# mapleCUL_small-V2_0_019.net
KiCad netlist of a schematic drawn in EAGLE
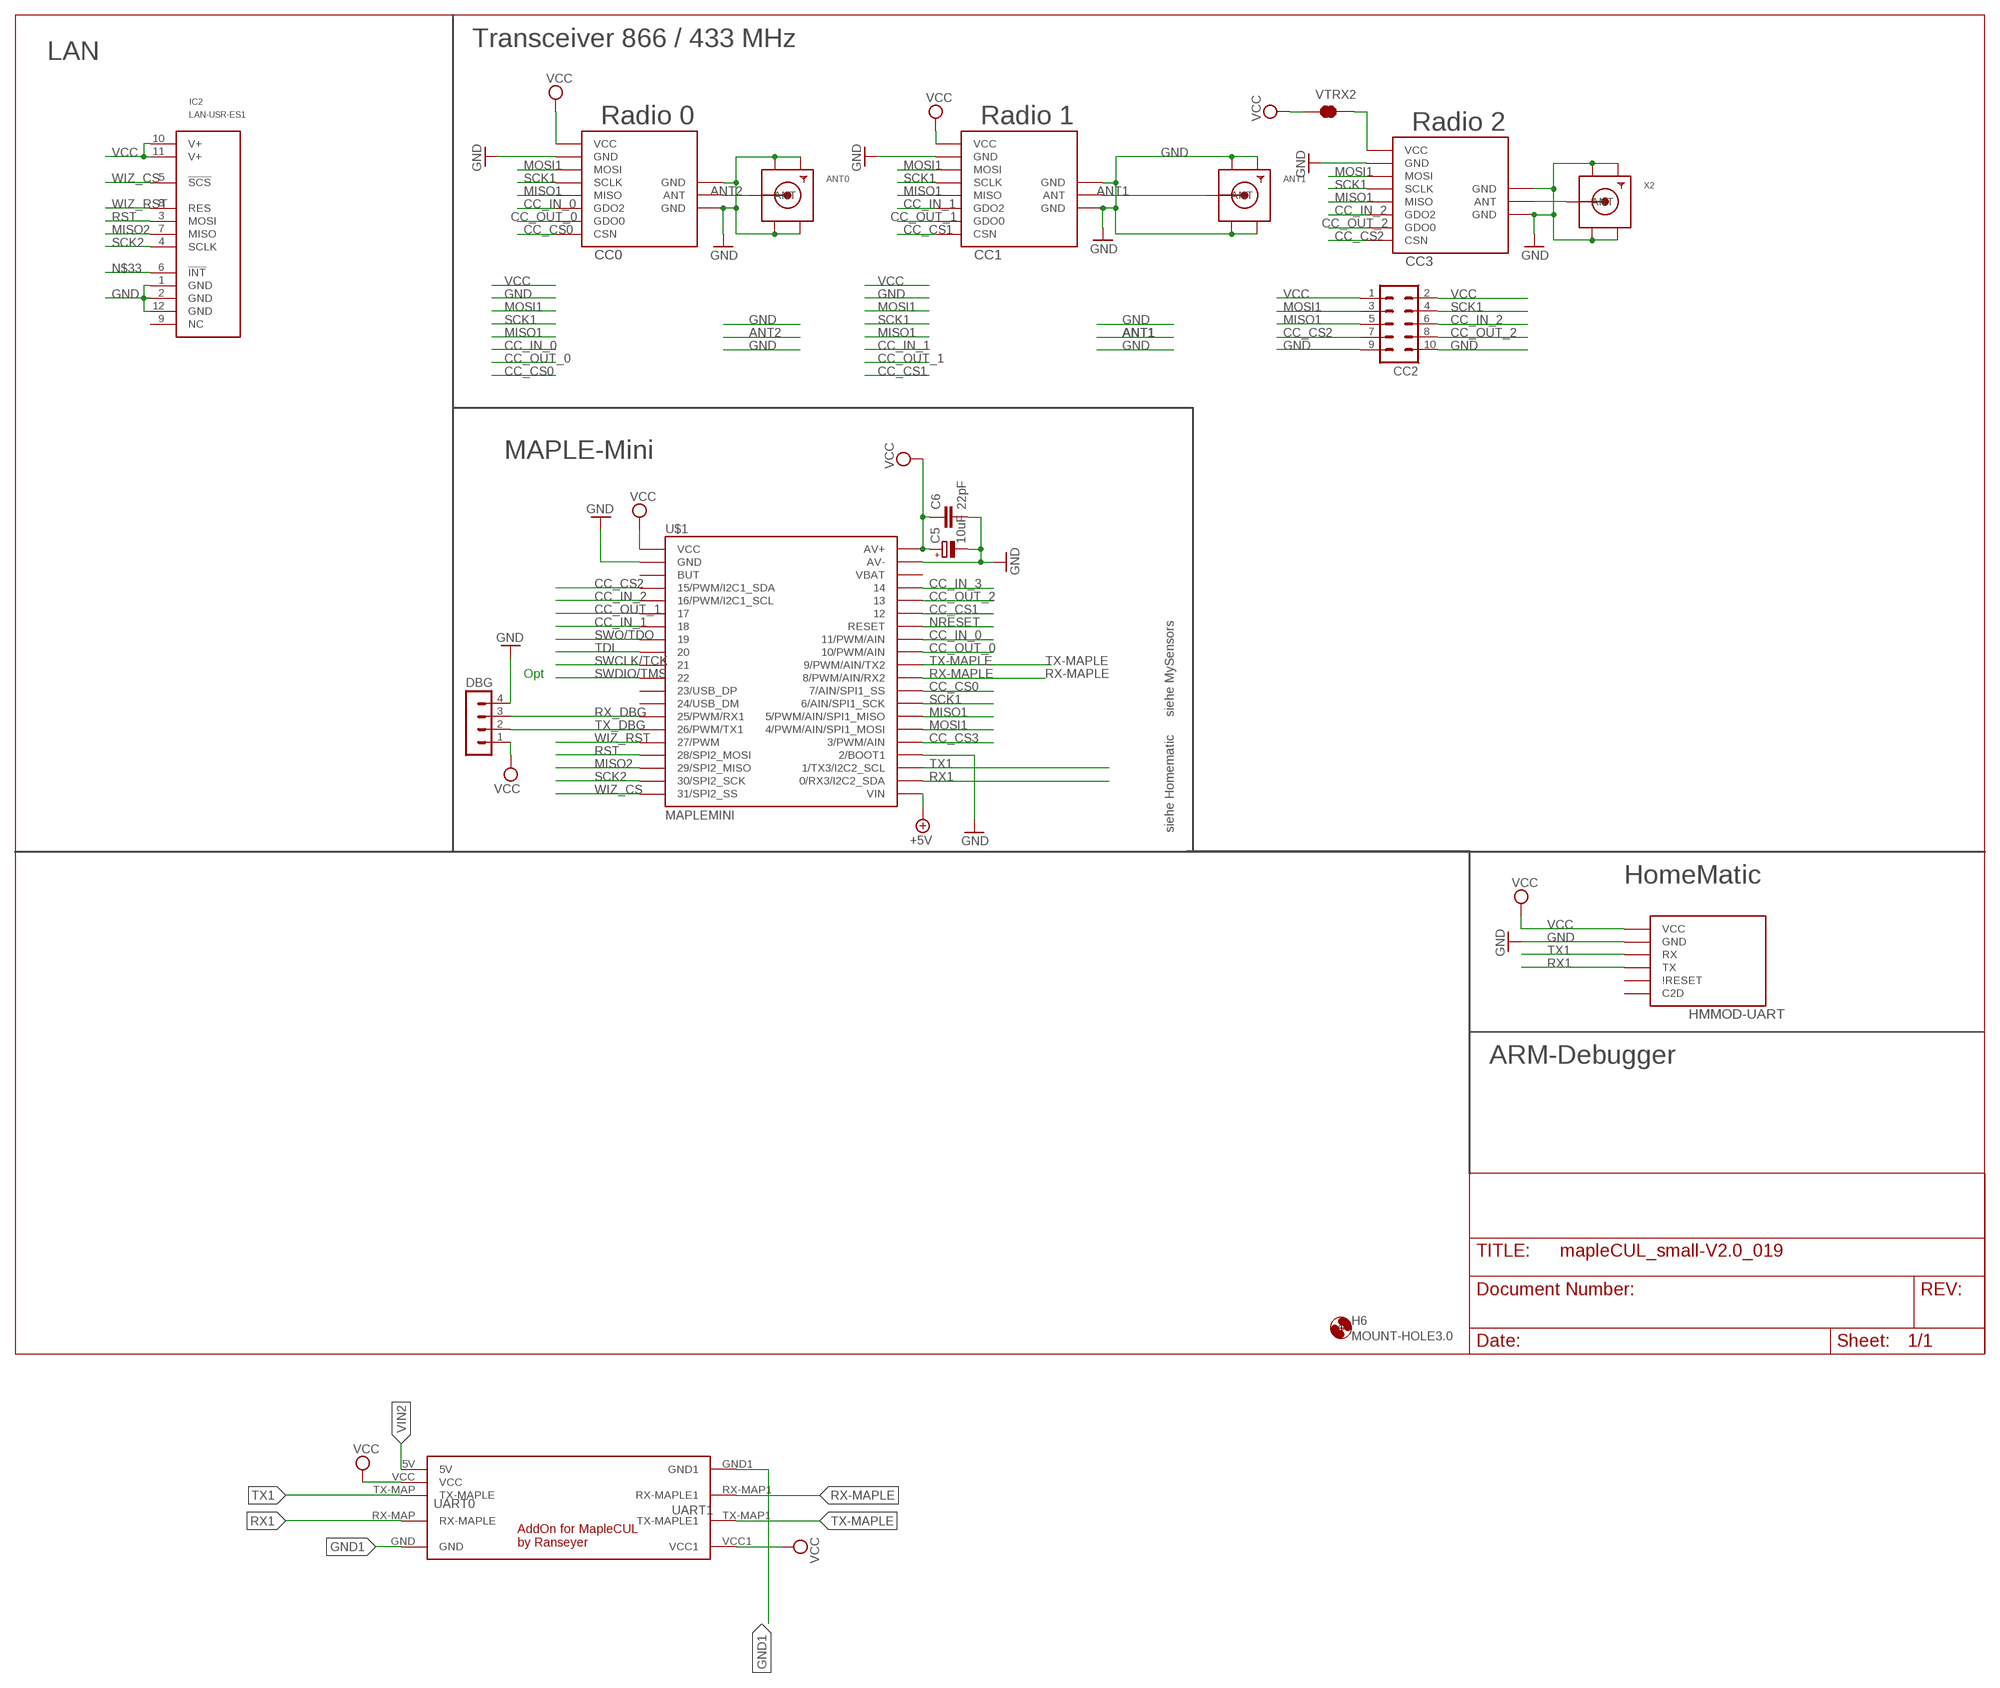
[diagram p0: schematic, sheet 1]

(export (version "E")
  (design (tool "Eeschema 10.0.6"))
  (components
    (comp (ref "ANT0")
      (value "SMACONNECTOR_EDGE_UFL")
      (footprint "eagle-import:SMA_EDGELAUNCH_UFL")
      (libsource (lib "eagle-import") (part "SMACONNECTOR_EDGE_UFL"))
    )
    (comp (ref "ANT1")
      (value "SMACONNECTOR_EDGE_UFL")
      (footprint "eagle-import:SMA_EDGELAUNCH_UFL")
      (libsource (lib "eagle-import") (part "SMACONNECTOR_EDGE_UFL"))
    )
    (comp (ref "C5")
      (value "10uF")
      (footprint "eagle-import:R_2012-12W")
      (libsource (lib "eagle-import") (part "CPOL-EUR/2012-12W"))
    )
    (comp (ref "C6")
      (value "22pF")
      (footprint "eagle-import:C0805")
      (libsource (lib "eagle-import") (part "C-EUC0805"))
    )
    (comp (ref "CC0")
      (value "CC1101")
      (footprint "eagle-import:CC1101_MODULE1_SMD")
      (libsource (lib "eagle-import") (part "CC1101_MODULE1SMD"))
    )
    (comp (ref "CC1")
      (value "CC1101_MODULE1SMD")
      (footprint "eagle-import:CC1101_MODULE1_SMD")
      (libsource (lib "eagle-import") (part "CC1101_MODULE1SMD"))
    )
    (comp (ref "CC2")
      (value "MA05-2")
      (footprint "eagle-import:MA05-2")
      (libsource (lib "eagle-import") (part "MA05-2"))
    )
    (comp (ref "CC3")
      (value "CC1101_MODULE1SMD")
      (footprint "eagle-import:CC1101_MODULE1_SMD")
      (libsource (lib "eagle-import") (part "CC1101_MODULE1SMD"))
    )
    (comp (ref "DBG")
      (value "MA04-1")
      (footprint "eagle-import:MA04-1")
      (libsource (lib "eagle-import") (part "MA04-1"))
    )
    (comp (ref "H6")
      (value "MOUNT-HOLE3.0")
      (footprint "eagle-import:3,0")
      (libsource (lib "eagle-import") (part "MOUNT-HOLE3.0"))
    )
    (comp (ref "HMMOD-UART")
      (value "HM-MOD-UARTDIL")
      (footprint "eagle-import:HM-MOD-UART-DIL")
      (libsource (lib "eagle-import") (part "HM-MOD-UARTDIL"))
    )
    (comp (ref "IC2")
      (value "LAN-USR-ES1")
      (footprint "eagle-import:USR-ES1")
      (libsource (lib "eagle-import") (part "LAN-USR-ES1"))
    )
    (comp (ref "U$1")
      (value "MAPLEMINI")
      (footprint "eagle-import:20-DIP")
      (libsource (lib "eagle-import") (part "MAPLEMINI"))
    )
    (comp (ref "U$3")
      (value "MAPLE-CUL-ADDON-V01")
      (footprint "eagle-import:MAPLE-CUL-V01")
      (libsource (lib "eagle-import") (part "MAPLE-CUL-ADDON-V01"))
    )
    (comp (ref "VTRX2")
      (value "JUMPER-SMT_2_NC_TRACE_SILK")
      (footprint "eagle-import:SMT-JUMPER_2_NC_TRACE_SILK")
      (libsource (lib "eagle-import") (part "JUMPER-SMT_2_NC_TRACE_SILK"))
    )
    (comp (ref "X2")
      (value "SMACONNECTOR_EDGE")
      (footprint "eagle-import:SMA_EDGELAUNCH")
      (libsource (lib "eagle-import") (part "SMACONNECTOR_EDGE"))
    )
  )
  (nets
    (net (code "1") (name "+5V") (class "Default")
      (node (ref "U$1") (pin "21") (pinfunction "VIN_21") (pintype "bidirectional"))
    )
    (net (code "2") (name "/ANT1") (class "Default")
      (node (ref "ANT1") (pin "P") (pinfunction "ANT_P") (pintype "bidirectional"))
      (node (ref "CC1") (pin "ANT") (pinfunction "ANT_ANT") (pintype "output"))
    )
    (net (code "3") (name "/ANT2") (class "Default")
      (node (ref "ANT0") (pin "P") (pinfunction "ANT_P") (pintype "bidirectional"))
      (node (ref "CC0") (pin "ANT") (pinfunction "ANT_ANT") (pintype "output"))
    )
    (net (code "4") (name "/CC_CS0") (class "Default")
      (node (ref "CC0") (pin "CSN") (pinfunction "CSN_CSN") (pintype "bidirectional"))
      (node (ref "U$1") (pin "29") (pinfunction "7/AIN/SPI1_SS_29") (pintype "bidirectional"))
    )
    (net (code "5") (name "/CC_CS1") (class "Default")
      (node (ref "CC1") (pin "CSN") (pinfunction "CSN_CSN") (pintype "bidirectional"))
      (node (ref "U$1") (pin "35") (pinfunction "12_35") (pintype "bidirectional"))
    )
    (net (code "6") (name "/CC_CS2") (class "Default")
      (node (ref "CC2") (pin "7") (pinfunction "7_7") (pintype "passive"))
      (node (ref "CC3") (pin "CSN") (pinfunction "CSN_CSN") (pintype "bidirectional"))
      (node (ref "U$1") (pin "4") (pinfunction "15/PWM/I2C1_SDA_4") (pintype "bidirectional"))
    )
    (net (code "7") (name "/CC_CS3") (class "Default")
      (node (ref "U$1") (pin "25") (pinfunction "3/PWM/AIN_25") (pintype "bidirectional"))
    )
    (net (code "8") (name "/CC_IN_0") (class "Default")
      (node (ref "CC0") (pin "GDO2") (pinfunction "GDO2_GDO2") (pintype "bidirectional"))
      (node (ref "U$1") (pin "33") (pinfunction "11/PWM/AIN_33") (pintype "bidirectional"))
    )
    (net (code "9") (name "/CC_IN_1") (class "Default")
      (node (ref "CC1") (pin "GDO2") (pinfunction "GDO2_GDO2") (pintype "bidirectional"))
      (node (ref "U$1") (pin "7") (pinfunction "18_7") (pintype "bidirectional"))
    )
    (net (code "10") (name "/CC_IN_2") (class "Default")
      (node (ref "CC2") (pin "6") (pinfunction "6_6") (pintype "passive"))
      (node (ref "CC3") (pin "GDO2") (pinfunction "GDO2_GDO2") (pintype "bidirectional"))
      (node (ref "U$1") (pin "5") (pinfunction "16/PWM/I2C1_SCL_5") (pintype "bidirectional"))
    )
    (net (code "11") (name "/CC_IN_3") (class "Default")
      (node (ref "U$1") (pin "37") (pinfunction "14_37") (pintype "bidirectional"))
    )
    (net (code "12") (name "/CC_OUT_0") (class "Default")
      (node (ref "CC0") (pin "GDO0") (pinfunction "GDO0_GDO0") (pintype "bidirectional"))
      (node (ref "U$1") (pin "32") (pinfunction "10/PWM/AIN_32") (pintype "bidirectional"))
    )
    (net (code "13") (name "/CC_OUT_1") (class "Default")
      (node (ref "CC1") (pin "GDO0") (pinfunction "GDO0_GDO0") (pintype "bidirectional"))
      (node (ref "U$1") (pin "6") (pinfunction "17_6") (pintype "bidirectional"))
    )
    (net (code "14") (name "/CC_OUT_2") (class "Default")
      (node (ref "CC2") (pin "8") (pinfunction "8_8") (pintype "passive"))
      (node (ref "CC3") (pin "GDO0") (pinfunction "GDO0_GDO0") (pintype "bidirectional"))
      (node (ref "U$1") (pin "36") (pinfunction "13_36") (pintype "bidirectional"))
    )
    (net (code "15") (name "/MISO1") (class "Default")
      (node (ref "CC0") (pin "MISO") (pinfunction "MISO_MISO") (pintype "bidirectional"))
      (node (ref "CC1") (pin "MISO") (pinfunction "MISO_MISO") (pintype "bidirectional"))
      (node (ref "CC2") (pin "5") (pinfunction "5_5") (pintype "passive"))
      (node (ref "CC3") (pin "MISO") (pinfunction "MISO_MISO") (pintype "bidirectional"))
      (node (ref "U$1") (pin "27") (pinfunction "5/PWM/AIN/SPI1_MISO_27") (pintype "bidirectional"))
    )
    (net (code "16") (name "/MISO2") (class "Default")
      (node (ref "IC2") (pin "7") (pinfunction "MISO_7") (pintype "bidirectional"))
      (node (ref "U$1") (pin "18") (pinfunction "29/SPI2_MISO_18") (pintype "bidirectional"))
    )
    (net (code "17") (name "/MOSI1") (class "Default")
      (node (ref "CC0") (pin "MOSI") (pinfunction "MOSI_MOSI") (pintype "bidirectional"))
      (node (ref "CC1") (pin "MOSI") (pinfunction "MOSI_MOSI") (pintype "bidirectional"))
      (node (ref "CC2") (pin "3") (pinfunction "3_3") (pintype "passive"))
      (node (ref "CC3") (pin "MOSI") (pinfunction "MOSI_MOSI") (pintype "bidirectional"))
      (node (ref "U$1") (pin "26") (pinfunction "4/PWM/AIN/SPI1_MOSI_26") (pintype "bidirectional"))
    )
    (net (code "18") (name "/N$33") (class "Default")
      (node (ref "IC2") (pin "6") (pinfunction "~{INT}_6") (pintype "output"))
    )
    (net (code "19") (name "/NRESET") (class "Default")
      (node (ref "U$1") (pin "34") (pinfunction "RESET_34") (pintype "bidirectional"))
    )
    (net (code "20") (name "/RST") (class "Default")
      (node (ref "IC2") (pin "3") (pinfunction "MOSI_3") (pintype "bidirectional"))
      (node (ref "U$1") (pin "17") (pinfunction "28/SPI2_MOSI_17") (pintype "bidirectional"))
    )
    (net (code "21") (name "/RX_DBG") (class "Default")
      (node (ref "DBG") (pin "3") (pinfunction "3_3") (pintype "passive"))
      (node (ref "U$1") (pin "14") (pinfunction "25/PWM/RX1_14") (pintype "bidirectional"))
    )
    (net (code "22") (name "/SCK1") (class "Default")
      (node (ref "CC0") (pin "SCLK") (pinfunction "SCLK_SCLK") (pintype "bidirectional"))
      (node (ref "CC1") (pin "SCLK") (pinfunction "SCLK_SCLK") (pintype "bidirectional"))
      (node (ref "CC2") (pin "4") (pinfunction "4_4") (pintype "passive"))
      (node (ref "CC3") (pin "SCLK") (pinfunction "SCLK_SCLK") (pintype "bidirectional"))
      (node (ref "U$1") (pin "28") (pinfunction "6/AIN/SPI1_SCK_28") (pintype "bidirectional"))
    )
    (net (code "23") (name "/SCK2") (class "Default")
      (node (ref "IC2") (pin "4") (pinfunction "SCLK_4") (pintype "input"))
      (node (ref "U$1") (pin "19") (pinfunction "30/SPI2_SCK_19") (pintype "bidirectional"))
    )
    (net (code "24") (name "/SWCLK{slash}TCK") (class "Default")
      (node (ref "U$1") (pin "10") (pinfunction "21_10") (pintype "bidirectional"))
    )
    (net (code "25") (name "/SWDIO{slash}TMS") (class "Default")
      (node (ref "U$1") (pin "11") (pinfunction "22_11") (pintype "bidirectional"))
    )
    (net (code "26") (name "/SWO{slash}TDO") (class "Default")
      (node (ref "U$1") (pin "8") (pinfunction "19_8") (pintype "bidirectional"))
    )
    (net (code "27") (name "/TDI") (class "Default")
      (node (ref "U$1") (pin "9") (pinfunction "20_9") (pintype "bidirectional"))
    )
    (net (code "28") (name "/TX_DBG") (class "Default")
      (node (ref "DBG") (pin "2") (pinfunction "2_2") (pintype "passive"))
      (node (ref "U$1") (pin "15") (pinfunction "26/PWM/TX1_15") (pintype "bidirectional"))
    )
    (net (code "29") (name "/WIZ_CS") (class "Default")
      (node (ref "IC2") (pin "5") (pinfunction "~{SCS}_5") (pintype "input"))
      (node (ref "U$1") (pin "20") (pinfunction "31/SPI2_SS_20") (pintype "bidirectional"))
    )
    (net (code "30") (name "/WIZ_RST") (class "Default")
      (node (ref "IC2") (pin "8") (pinfunction "RES_8") (pintype "input"))
      (node (ref "U$1") (pin "16") (pinfunction "27/PWM_16") (pintype "bidirectional"))
    )
    (net (code "31") (name "GND") (class "Default")
      (node (ref "ANT0") (pin "GND@1") (pinfunction "GND1_GND@1") (pintype "power_in"))
      (node (ref "ANT0") (pin "GND@2") (pinfunction "GND2_GND@2") (pintype "power_in"))
      (node (ref "ANT0") (pin "GND@3") (pinfunction "GND3_GND@3") (pintype "power_in"))
      (node (ref "ANT0") (pin "GND@4") (pinfunction "GND4_GND@4") (pintype "power_in"))
      (node (ref "ANT1") (pin "GND@1") (pinfunction "GND1_GND@1") (pintype "power_in"))
      (node (ref "ANT1") (pin "GND@2") (pinfunction "GND2_GND@2") (pintype "power_in"))
      (node (ref "ANT1") (pin "GND@3") (pinfunction "GND3_GND@3") (pintype "power_in"))
      (node (ref "ANT1") (pin "GND@4") (pinfunction "GND4_GND@4") (pintype "power_in"))
      (node (ref "C5") (pin "-") (pinfunction "-_-") (pintype "passive"))
      (node (ref "C6") (pin "2") (pinfunction "2_2") (pintype "passive"))
      (node (ref "CC0") (pin "GND@0") (pinfunction "GND_GND@0") (pintype "power_in"))
      (node (ref "CC0") (pin "GND@1") (pinfunction "GND_GND@1") (pintype "power_in"))
      (node (ref "CC0") (pin "GND@2") (pinfunction "GND_GND@2") (pintype "power_in"))
      (node (ref "CC1") (pin "GND@0") (pinfunction "GND_GND@0") (pintype "power_in"))
      (node (ref "CC1") (pin "GND@1") (pinfunction "GND_GND@1") (pintype "power_in"))
      (node (ref "CC1") (pin "GND@2") (pinfunction "GND_GND@2") (pintype "power_in"))
      (node (ref "CC2") (pin "10") (pinfunction "10_10") (pintype "passive"))
      (node (ref "CC2") (pin "9") (pinfunction "9_9") (pintype "passive"))
      (node (ref "CC3") (pin "GND@0") (pinfunction "GND_GND@0") (pintype "power_in"))
      (node (ref "CC3") (pin "GND@1") (pinfunction "GND_GND@1") (pintype "power_in"))
      (node (ref "CC3") (pin "GND@2") (pinfunction "GND_GND@2") (pintype "power_in"))
      (node (ref "DBG") (pin "4") (pinfunction "4_4") (pintype "passive"))
      (node (ref "HMMOD-UART") (pin "2") (pinfunction "GND_2") (pintype "power_in"))
      (node (ref "IC2") (pin "1") (pinfunction "GND_1") (pintype "power_in"))
      (node (ref "IC2") (pin "12") (pinfunction "GND_12") (pintype "power_in"))
      (node (ref "IC2") (pin "2") (pinfunction "GND_2") (pintype "power_in"))
      (node (ref "U$1") (pin "2") (pinfunction "GND_2") (pintype "bidirectional"))
      (node (ref "U$1") (pin "24") (pinfunction "2/BOOT1_24") (pintype "bidirectional"))
      (node (ref "U$1") (pin "39") (pinfunction "AV-_39") (pintype "bidirectional"))
      (node (ref "X2") (pin "GND@1") (pinfunction "GND4_GND@1") (pintype "power_in"))
      (node (ref "X2") (pin "GND@2") (pinfunction "GND3_GND@2") (pintype "power_in"))
      (node (ref "X2") (pin "GND@3") (pinfunction "GND2_GND@3") (pintype "power_in"))
      (node (ref "X2") (pin "GND@4") (pinfunction "GND1_GND@4") (pintype "power_in"))
    )
    (net (code "32") (name "GND1") (class "Default")
      (node (ref "U$3") (pin "GND") (pinfunction "GND_GND") (pintype "bidirectional"))
      (node (ref "U$3") (pin "GND1") (pinfunction "GND1_GND1") (pintype "bidirectional"))
    )
    (net (code "33") (name "Net-(CC3-PadVCC)") (class "Default")
      (node (ref "CC3") (pin "VCC") (pinfunction "VCC_VCC") (pintype "power_in"))
      (node (ref "VTRX2") (pin "2") (pinfunction "2_2") (pintype "passive"))
    )
    (net (code "34") (name "Net-(X2-ANT)") (class "Default")
      (node (ref "CC3") (pin "ANT") (pinfunction "ANT_ANT") (pintype "output"))
      (node (ref "X2") (pin "P") (pinfunction "ANT_P") (pintype "bidirectional"))
    )
    (net (code "35") (name "RX-MAPLE") (class "Default")
      (node (ref "U$1") (pin "30") (pinfunction "8/PWM/AIN/RX2_30") (pintype "bidirectional"))
      (node (ref "U$3") (pin "RX-MAP1") (pinfunction "RX-MAPLE1_RX-MAP1") (pintype "bidirectional"))
    )
    (net (code "36") (name "RX1") (class "Default")
      (node (ref "HMMOD-UART") (pin "5") (pinfunction "TX_5") (pintype "bidirectional"))
      (node (ref "U$1") (pin "22") (pinfunction "0/RX3/I2C2_SDA_22") (pintype "bidirectional"))
      (node (ref "U$3") (pin "RX-MAP") (pinfunction "RX-MAPLE_RX-MAP") (pintype "bidirectional"))
    )
    (net (code "37") (name "TX-MAPLE") (class "Default")
      (node (ref "U$1") (pin "31") (pinfunction "9/PWM/AIN/TX2_31") (pintype "bidirectional"))
      (node (ref "U$3") (pin "TX-MAP1") (pinfunction "TX-MAPLE1_TX-MAP1") (pintype "bidirectional"))
    )
    (net (code "38") (name "TX1") (class "Default")
      (node (ref "HMMOD-UART") (pin "6") (pinfunction "RX_6") (pintype "bidirectional"))
      (node (ref "U$1") (pin "23") (pinfunction "1/TX3/I2C2_SCL_23") (pintype "bidirectional"))
      (node (ref "U$3") (pin "TX-MAP") (pinfunction "TX-MAPLE_TX-MAP") (pintype "bidirectional"))
    )
    (net (code "39") (name "VCC") (class "Default")
      (node (ref "C5") (pin "+") (pinfunction "+_+") (pintype "passive"))
      (node (ref "C6") (pin "1") (pinfunction "1_1") (pintype "passive"))
      (node (ref "CC0") (pin "VCC") (pinfunction "VCC_VCC") (pintype "power_in"))
      (node (ref "CC1") (pin "VCC") (pinfunction "VCC_VCC") (pintype "power_in"))
      (node (ref "CC2") (pin "1") (pinfunction "1_1") (pintype "passive"))
      (node (ref "CC2") (pin "2") (pinfunction "2_2") (pintype "passive"))
      (node (ref "DBG") (pin "1") (pinfunction "1_1") (pintype "passive"))
      (node (ref "HMMOD-UART") (pin "1") (pinfunction "VCC_1") (pintype "power_in"))
      (node (ref "IC2") (pin "10") (pinfunction "V+_10") (pintype "power_in"))
      (node (ref "IC2") (pin "11") (pinfunction "V+_11") (pintype "power_in"))
      (node (ref "U$1") (pin "1") (pinfunction "VCC_1") (pintype "bidirectional"))
      (node (ref "U$1") (pin "40") (pinfunction "AV+_40") (pintype "bidirectional"))
      (node (ref "U$3") (pin "VCC") (pinfunction "VCC_VCC") (pintype "bidirectional"))
      (node (ref "U$3") (pin "VCC1") (pinfunction "VCC1_VCC1") (pintype "bidirectional"))
      (node (ref "VTRX2") (pin "1") (pinfunction "1_1") (pintype "passive"))
    )
    (net (code "40") (name "VIN2") (class "Default")
      (node (ref "U$3") (pin "5V") (pinfunction "5V_5V") (pintype "bidirectional"))
    )
    (net (code "41") (name "unconnected-(HMMOD-UART-C2D-Pad3)") (class "Default")
      (node (ref "HMMOD-UART") (pin "3") (pinfunction "C2D_3") (pintype "bidirectional"))
    )
    (net (code "42") (name "unconnected-(HMMOD-UART-\\~{RESET}-Pad4)") (class "Default")
      (node (ref "HMMOD-UART") (pin "4") (pinfunction "\\~{RESET}_4") (pintype "bidirectional"))
    )
    (net (code "43") (name "unconnected-(IC2-NC-Pad9)") (class "Default")
      (node (ref "IC2") (pin "9") (pinfunction "NC_9") (pintype "no_connect"))
    )
    (net (code "44") (name "unconnected-(U$1-23{slash}USB_DP-Pad12)") (class "Default")
      (node (ref "U$1") (pin "12") (pinfunction "23/USB_DP_12") (pintype "bidirectional"))
    )
    (net (code "45") (name "unconnected-(U$1-24{slash}USB_DM-Pad13)") (class "Default")
      (node (ref "U$1") (pin "13") (pinfunction "24/USB_DM_13") (pintype "bidirectional"))
    )
    (net (code "46") (name "unconnected-(U$1-BUT-Pad3)") (class "Default")
      (node (ref "U$1") (pin "3") (pinfunction "BUT_3") (pintype "bidirectional"))
    )
    (net (code "47") (name "unconnected-(U$1-VBAT-Pad38)") (class "Default")
      (node (ref "U$1") (pin "38") (pinfunction "VBAT_38") (pintype "bidirectional"))
    )
  )
)
